# Sequencer-V10-024.net
KiCad netlist of a schematic drawn in EAGLE
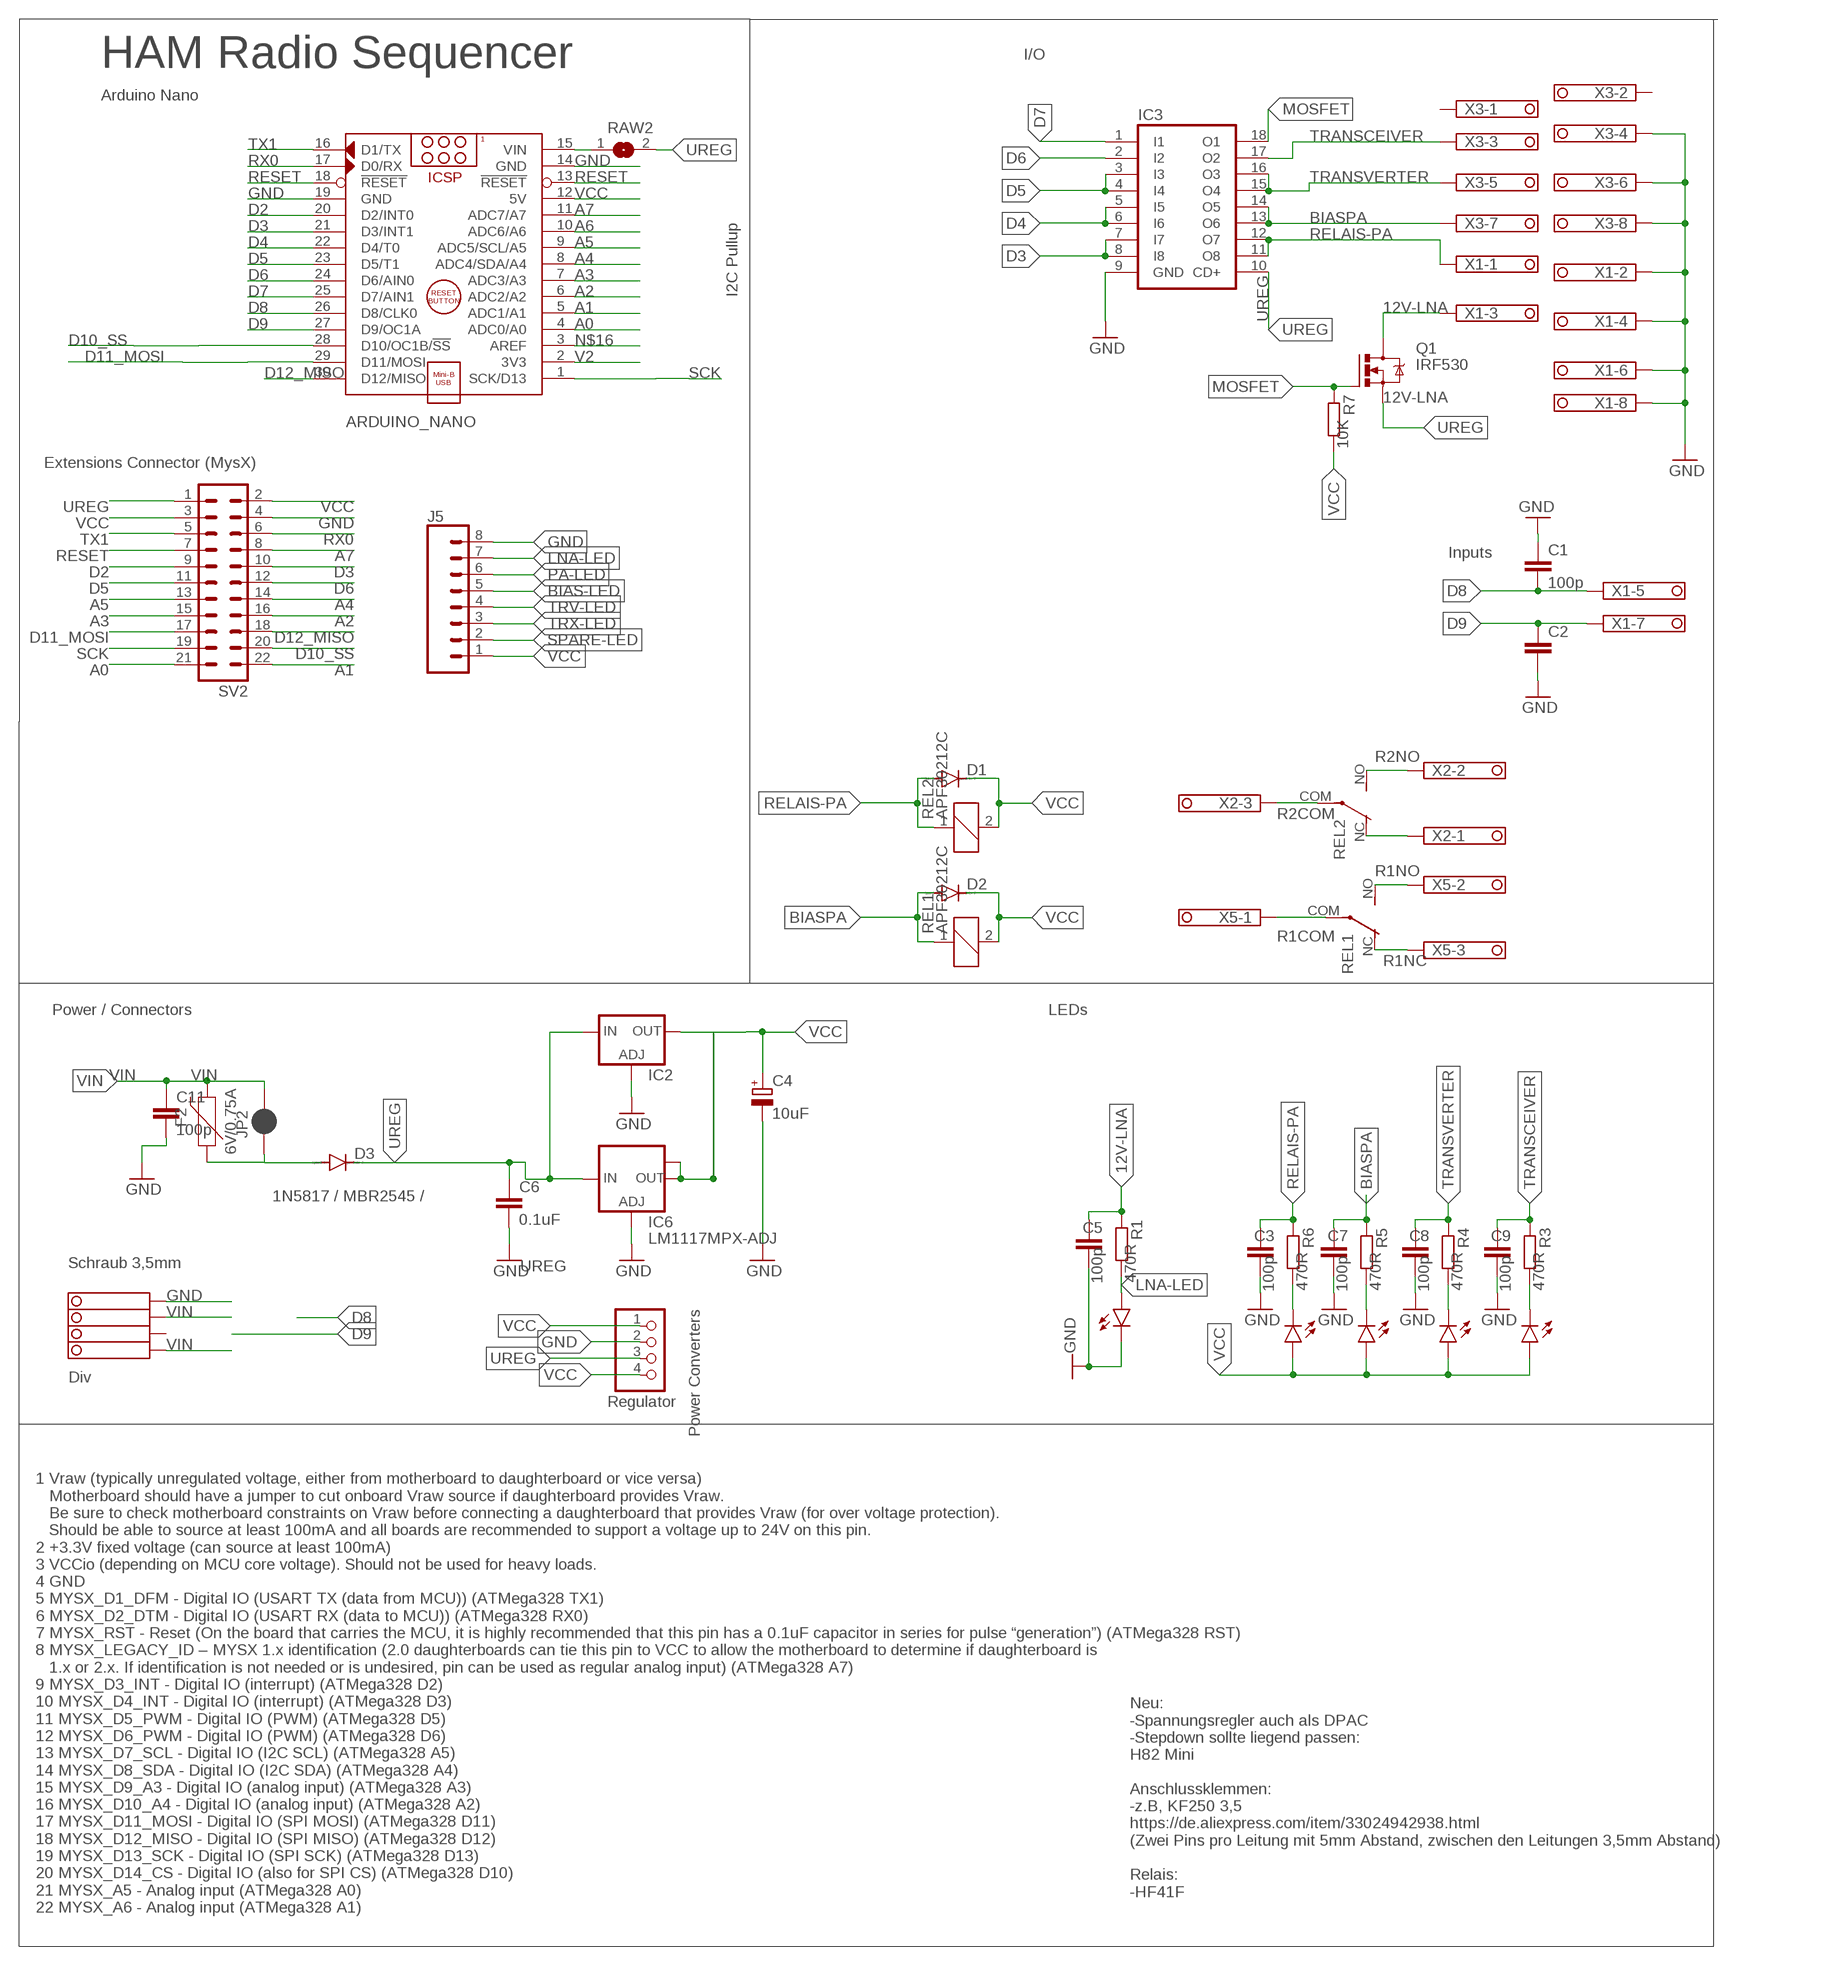
[diagram p0: schematic, sheet 1]

(export (version "E")
  (design (tool "Eeschema 10.0.6"))
  (components
    (comp (ref "ARDUINO_NANO")
      (value "ARDUINO_NANO_OHNE-BOHR")
      (footprint "eagle-import:ARDUINO_NANO")
      (libsource (lib "eagle-import") (part "ARDUINO_NANO_OHNE-BOHR"))
    )
    (comp (ref "C1")
      (value "100p")
      (footprint "eagle-import:C025-025X050")
      (libsource (lib "eagle-import") (part "C-EU025-025X050"))
    )
    (comp (ref "C2")
      (value "C-EU025-025X050")
      (footprint "eagle-import:C025-025X050")
      (libsource (lib "eagle-import") (part "C-EU025-025X050"))
    )
    (comp (ref "C3")
      (value "100p")
      (footprint "eagle-import:C025-025X050")
      (libsource (lib "eagle-import") (part "C-EU025-025X050"))
    )
    (comp (ref "C4")
      (value "10uF")
      (footprint "eagle-import:E3,5-8")
      (libsource (lib "eagle-import") (part "CPOL-EUE3.5-8"))
    )
    (comp (ref "C5")
      (value "100p")
      (footprint "eagle-import:C025-025X050")
      (libsource (lib "eagle-import") (part "C-EU025-025X050"))
    )
    (comp (ref "C6")
      (value "0.1uF")
      (footprint "eagle-import:C050-024X044")
      (libsource (lib "eagle-import") (part "C-EU050-024X044"))
    )
    (comp (ref "C7")
      (value "100p")
      (footprint "eagle-import:C025-025X050")
      (libsource (lib "eagle-import") (part "C-EU025-025X050"))
    )
    (comp (ref "C8")
      (value "100p")
      (footprint "eagle-import:C025-025X050")
      (libsource (lib "eagle-import") (part "C-EU025-025X050"))
    )
    (comp (ref "C9")
      (value "100p")
      (footprint "eagle-import:C025-025X050")
      (libsource (lib "eagle-import") (part "C-EU025-025X050"))
    )
    (comp (ref "C11")
      (value "100p")
      (footprint "eagle-import:C025-025X050")
      (libsource (lib "eagle-import") (part "C-EU025-025X050"))
    )
    (comp (ref "D1")
      (value "DIODE-D-2.5")
      (footprint "eagle-import:D-2.5")
      (libsource (lib "eagle-import") (part "DIODE-D-2.5"))
    )
    (comp (ref "D2")
      (value "DIODE-D-2.5")
      (footprint "eagle-import:D-2.5")
      (libsource (lib "eagle-import") (part "DIODE-D-2.5"))
    )
    (comp (ref "D3")
      (value "1N5817 / MBR2545 /")
      (footprint "eagle-import:D-7.5")
      (libsource (lib "eagle-import") (part "DIODE-D-7.5"))
    )
    (comp (ref "F2")
      (value "6V/0.75A")
      (footprint "eagle-import:1206")
      (libsource (lib "eagle-import") (part "PPTC_THREE-QUARTER-AMP"))
    )
    (comp (ref "IC2")
      (value "LD117ADT50TR")
      (footprint "eagle-import:DPACK")
      (libsource (lib "eagle-import") (part "LD117A?DT50TR"))
    )
    (comp (ref "IC3")
      (value "ULN2803A")
      (footprint "eagle-import:DIL18")
      (libsource (lib "eagle-import") (part "ULN2803A"))
    )
    (comp (ref "IC6")
      (value "LM1117MPX-ADJ")
      (footprint "eagle-import:SOT223")
      (libsource (lib "eagle-import") (part "LM1117MPX-ADJ"))
    )
    (comp (ref "J5")
      (value "CONN_08LOCK")
      (footprint "eagle-import:1X08_LOCK")
      (libsource (lib "eagle-import") (part "CONN_08LOCK"))
    )
    (comp (ref "JP2")
      (value "JUMPER-SMT_2_NC_PASTE_NO-SILK")
      (footprint "eagle-import:SMT-JUMPER_2_NC_PASTE_NO-SILK")
      (libsource (lib "eagle-import") (part "JUMPER-SMT_2_NC_PASTE_NO-SILK"))
    )
    (comp (ref "LED-BIAS")
      (value "LED3MM")
      (footprint "eagle-import:LED3MM")
      (libsource (lib "eagle-import") (part "LED3MM"))
    )
    (comp (ref "LED-LNA")
      (value "LED3MM")
      (footprint "eagle-import:LED3MM")
      (libsource (lib "eagle-import") (part "LED3MM"))
    )
    (comp (ref "LED-PA")
      (value "LED3MM")
      (footprint "eagle-import:LED3MM")
      (libsource (lib "eagle-import") (part "LED3MM"))
    )
    (comp (ref "LED-TRV")
      (value "LED3MM")
      (footprint "eagle-import:LED3MM")
      (libsource (lib "eagle-import") (part "LED3MM"))
    )
    (comp (ref "LED-TRX")
      (value "LED3MM")
      (footprint "eagle-import:LED3MM")
      (libsource (lib "eagle-import") (part "LED3MM"))
    )
    (comp (ref "Q1")
      (value "IRF530")
      (footprint "eagle-import:TO220BV")
      (libsource (lib "eagle-import") (part "IRF530"))
    )
    (comp (ref "R1")
      (value "470R")
      (footprint "eagle-import:0207_7")
      (libsource (lib "eagle-import") (part "R-EU_0207/7"))
    )
    (comp (ref "R3")
      (value "470R")
      (footprint "eagle-import:0207_7")
      (libsource (lib "eagle-import") (part "R-EU_0207/7"))
    )
    (comp (ref "R4")
      (value "470R")
      (footprint "eagle-import:0207_7")
      (libsource (lib "eagle-import") (part "R-EU_0207/7"))
    )
    (comp (ref "R5")
      (value "470R")
      (footprint "eagle-import:0207_7")
      (libsource (lib "eagle-import") (part "R-EU_0207/7"))
    )
    (comp (ref "R6")
      (value "470R")
      (footprint "eagle-import:0207_7")
      (libsource (lib "eagle-import") (part "R-EU_0207/7"))
    )
    (comp (ref "R7")
      (value "10K")
      (footprint "eagle-import:0207_7")
      (libsource (lib "eagle-import") (part "R-EU_0207/7"))
    )
    (comp (ref "RAW2")
      (value "SJ")
      (footprint "eagle-import:SJ")
      (libsource (lib "eagle-import") (part "SJ"))
    )
    (comp (ref "REL1")
      (value "APF30212C")
      (footprint "eagle-import:APF30212C")
      (libsource (lib "eagle-import") (part "APF30212C"))
    )
    (comp (ref "REL2")
      (value "APF30212C")
      (footprint "eagle-import:APF30212C")
      (libsource (lib "eagle-import") (part "APF30212C"))
    )
    (comp (ref "STEPDWN")
      (value "PINHD-1X04_2.54-S")
      (footprint "eagle-import:1X04-S")
      (libsource (lib "eagle-import") (part "PINHD-1X04_2.54-S"))
    )
    (comp (ref "SV2")
      (value "MA11-2")
      (footprint "eagle-import:MA11-2")
      (libsource (lib "eagle-import") (part "MA11-2"))
    )
    (comp (ref "X1")
      (value "MARTIN8X2-1751303")
      (footprint "eagle-import:1751303")
      (libsource (lib "eagle-import") (part "MARTIN8X2-1751303"))
    )
    (comp (ref "X2")
      (value "MARTIN3X2-1751303175L303-3")
      (footprint "eagle-import:1751303-3")
      (libsource (lib "eagle-import") (part "MARTIN3X2-1751303175L303-3"))
    )
    (comp (ref "X3")
      (value "MARTIN8X2-1751303")
      (footprint "eagle-import:1751303")
      (libsource (lib "eagle-import") (part "MARTIN8X2-1751303"))
    )
    (comp (ref "X4")
      (value "1751264")
      (footprint "eagle-import:1751264")
      (libsource (lib "eagle-import") (part "1751264"))
    )
    (comp (ref "X5")
      (value "MARTIN3X2-1751303175L303-3")
      (footprint "eagle-import:1751303-3")
      (libsource (lib "eagle-import") (part "MARTIN3X2-1751303175L303-3"))
    )
  )
  (nets
    (net (code "1") (name "/A0") (class "Default")
      (node (ref "ARDUINO_NANO") (pin "4") (pinfunction "ADC0/A0_4") (pintype "bidirectional"))
      (node (ref "SV2") (pin "21") (pinfunction "21_21") (pintype "passive"))
    )
    (net (code "2") (name "/A1") (class "Default")
      (node (ref "ARDUINO_NANO") (pin "5") (pinfunction "ADC1/A1_5") (pintype "bidirectional"))
      (node (ref "SV2") (pin "22") (pinfunction "22_22") (pintype "passive"))
    )
    (net (code "3") (name "/A2") (class "Default")
      (node (ref "ARDUINO_NANO") (pin "6") (pinfunction "ADC2/A2_6") (pintype "bidirectional"))
      (node (ref "SV2") (pin "16") (pinfunction "16_16") (pintype "passive"))
    )
    (net (code "4") (name "/A3") (class "Default")
      (node (ref "ARDUINO_NANO") (pin "7") (pinfunction "ADC3/A3_7") (pintype "bidirectional"))
      (node (ref "SV2") (pin "15") (pinfunction "15_15") (pintype "passive"))
    )
    (net (code "5") (name "/A4") (class "Default")
      (node (ref "ARDUINO_NANO") (pin "8") (pinfunction "ADC4/SDA/A4_8") (pintype "bidirectional"))
      (node (ref "SV2") (pin "14") (pinfunction "14_14") (pintype "passive"))
    )
    (net (code "6") (name "/A5") (class "Default")
      (node (ref "ARDUINO_NANO") (pin "9") (pinfunction "ADC5/SCL/A5_9") (pintype "bidirectional"))
      (node (ref "SV2") (pin "13") (pinfunction "13_13") (pintype "passive"))
    )
    (net (code "7") (name "/A6") (class "Default")
      (node (ref "ARDUINO_NANO") (pin "10") (pinfunction "ADC6/A6_10") (pintype "bidirectional"))
    )
    (net (code "8") (name "/A7") (class "Default")
      (node (ref "ARDUINO_NANO") (pin "11") (pinfunction "ADC7/A7_11") (pintype "bidirectional"))
      (node (ref "SV2") (pin "8") (pinfunction "8_8") (pintype "passive"))
    )
    (net (code "9") (name "/D2") (class "Default")
      (node (ref "ARDUINO_NANO") (pin "20") (pinfunction "D2/INT0_20") (pintype "bidirectional"))
      (node (ref "SV2") (pin "9") (pinfunction "9_9") (pintype "passive"))
    )
    (net (code "10") (name "/D10_SS") (class "Default")
      (node (ref "ARDUINO_NANO") (pin "28") (pinfunction "D10/OC1B/~{SS}_28") (pintype "bidirectional"))
      (node (ref "SV2") (pin "20") (pinfunction "20_20") (pintype "passive"))
    )
    (net (code "11") (name "/D11_MOSI") (class "Default")
      (node (ref "ARDUINO_NANO") (pin "29") (pinfunction "D11/MOSI_29") (pintype "bidirectional"))
      (node (ref "SV2") (pin "17") (pinfunction "17_17") (pintype "passive"))
    )
    (net (code "12") (name "/D12_MISO") (class "Default")
      (node (ref "ARDUINO_NANO") (pin "30") (pinfunction "D12/MISO_30") (pintype "bidirectional"))
      (node (ref "SV2") (pin "18") (pinfunction "18_18") (pintype "passive"))
    )
    (net (code "13") (name "/N$16") (class "Default")
      (node (ref "ARDUINO_NANO") (pin "3") (pinfunction "AREF_3") (pintype "input"))
    )
    (net (code "14") (name "/R1COM") (class "Default")
      (node (ref "REL1") (pin "COM") (pinfunction "P_COM") (pintype "passive"))
      (node (ref "X5") (pin "1") (pinfunction "K_1") (pintype "passive"))
    )
    (net (code "15") (name "/R1NC") (class "Default")
      (node (ref "REL1") (pin "NC") (pinfunction "O_NC") (pintype "passive"))
      (node (ref "X5") (pin "3") (pinfunction "K_3") (pintype "passive"))
    )
    (net (code "16") (name "/R1NO") (class "Default")
      (node (ref "REL1") (pin "NO") (pinfunction "S_NO") (pintype "passive"))
      (node (ref "X5") (pin "2") (pinfunction "K_2") (pintype "passive"))
    )
    (net (code "17") (name "/R2COM") (class "Default")
      (node (ref "REL2") (pin "COM") (pinfunction "P_COM") (pintype "passive"))
      (node (ref "X2") (pin "3") (pinfunction "K_3") (pintype "passive"))
    )
    (net (code "18") (name "/R2NO") (class "Default")
      (node (ref "REL2") (pin "NO") (pinfunction "S_NO") (pintype "passive"))
      (node (ref "X2") (pin "2") (pinfunction "K_2") (pintype "passive"))
    )
    (net (code "19") (name "/RESET") (class "Default")
      (node (ref "ARDUINO_NANO") (pin "13") (pinfunction "~{RESET}_13") (pintype "input"))
      (node (ref "ARDUINO_NANO") (pin "18") (pinfunction "~{RESET}_18") (pintype "input"))
      (node (ref "SV2") (pin "7") (pinfunction "7_7") (pintype "passive"))
    )
    (net (code "20") (name "/RX0") (class "Default")
      (node (ref "ARDUINO_NANO") (pin "17") (pinfunction "D0/RX_17") (pintype "bidirectional"))
      (node (ref "SV2") (pin "6") (pinfunction "6_6") (pintype "passive"))
    )
    (net (code "21") (name "/SCK") (class "Default")
      (node (ref "ARDUINO_NANO") (pin "1") (pinfunction "SCK/D13_1") (pintype "bidirectional"))
      (node (ref "SV2") (pin "19") (pinfunction "19_19") (pintype "passive"))
    )
    (net (code "22") (name "/TX1") (class "Default")
      (node (ref "ARDUINO_NANO") (pin "16") (pinfunction "D1/TX_16") (pintype "bidirectional"))
      (node (ref "SV2") (pin "5") (pinfunction "5_5") (pintype "passive"))
    )
    (net (code "23") (name "/V2") (class "Default")
      (node (ref "ARDUINO_NANO") (pin "2") (pinfunction "3V3_2") (pintype "output"))
    )
    (net (code "24") (name "12V-LNA") (class "Default")
      (node (ref "C5") (pin "1") (pinfunction "1_1") (pintype "passive"))
      (node (ref "Q1") (pin "D") (pinfunction "D_D") (pintype "passive"))
      (node (ref "R1") (pin "1") (pinfunction "1_1") (pintype "passive"))
      (node (ref "X1") (pin "11") (pinfunction "K_11") (pintype "passive"))
    )
    (net (code "25") (name "BIAS-LED") (class "Default")
      (node (ref "J5") (pin "5") (pinfunction "5_5") (pintype "passive"))
      (node (ref "LED-BIAS") (pin "K") (pinfunction "C_K") (pintype "passive"))
      (node (ref "R5") (pin "2") (pinfunction "2_2") (pintype "passive"))
    )
    (net (code "26") (name "BIASPA") (class "Default")
      (node (ref "C7") (pin "1") (pinfunction "1_1") (pintype "passive"))
      (node (ref "D2") (pin "A") (pinfunction "A_A") (pintype "passive"))
      (node (ref "IC3") (pin "13") (pinfunction "O6_13") (pintype "open_collector"))
      (node (ref "IC3") (pin "14") (pinfunction "O5_14") (pintype "open_collector"))
      (node (ref "R5") (pin "1") (pinfunction "1_1") (pintype "passive"))
      (node (ref "REL1") (pin "1") (pinfunction "1_1") (pintype "passive"))
      (node (ref "X3") (pin "15") (pinfunction "K_15") (pintype "passive"))
    )
    (net (code "27") (name "D3") (class "Default")
      (node (ref "ARDUINO_NANO") (pin "21") (pinfunction "D3/INT1_21") (pintype "bidirectional"))
      (node (ref "IC3") (pin "7") (pinfunction "I7_7") (pintype "input"))
      (node (ref "IC3") (pin "8") (pinfunction "I8_8") (pintype "input"))
      (node (ref "SV2") (pin "10") (pinfunction "10_10") (pintype "passive"))
    )
    (net (code "28") (name "D4") (class "Default")
      (node (ref "ARDUINO_NANO") (pin "22") (pinfunction "D4/T0_22") (pintype "bidirectional"))
      (node (ref "IC3") (pin "5") (pinfunction "I5_5") (pintype "input"))
      (node (ref "IC3") (pin "6") (pinfunction "I6_6") (pintype "input"))
    )
    (net (code "29") (name "D5") (class "Default")
      (node (ref "ARDUINO_NANO") (pin "23") (pinfunction "D5/T1_23") (pintype "bidirectional"))
      (node (ref "IC3") (pin "3") (pinfunction "I3_3") (pintype "input"))
      (node (ref "IC3") (pin "4") (pinfunction "I4_4") (pintype "input"))
      (node (ref "SV2") (pin "11") (pinfunction "11_11") (pintype "passive"))
    )
    (net (code "30") (name "D6") (class "Default")
      (node (ref "ARDUINO_NANO") (pin "24") (pinfunction "D6/AIN0_24") (pintype "bidirectional"))
      (node (ref "IC3") (pin "2") (pinfunction "I2_2") (pintype "input"))
      (node (ref "SV2") (pin "12") (pinfunction "12_12") (pintype "passive"))
    )
    (net (code "31") (name "D7") (class "Default")
      (node (ref "ARDUINO_NANO") (pin "25") (pinfunction "D7/AIN1_25") (pintype "bidirectional"))
      (node (ref "IC3") (pin "1") (pinfunction "I1_1") (pintype "input"))
    )
    (net (code "32") (name "D8") (class "Default")
      (node (ref "ARDUINO_NANO") (pin "26") (pinfunction "D8/CLK0_26") (pintype "bidirectional"))
      (node (ref "C1") (pin "2") (pinfunction "2_2") (pintype "passive"))
      (node (ref "X1") (pin "13") (pinfunction "K_13") (pintype "passive"))
    )
    (net (code "33") (name "D9") (class "Default")
      (node (ref "ARDUINO_NANO") (pin "27") (pinfunction "D9/OC1A_27") (pintype "bidirectional"))
      (node (ref "C2") (pin "1") (pinfunction "1_1") (pintype "passive"))
      (node (ref "X1") (pin "15") (pinfunction "K_15") (pintype "passive"))
    )
    (net (code "34") (name "GND") (class "Default")
      (node (ref "ARDUINO_NANO") (pin "14") (pinfunction "GND_14") (pintype "power_in"))
      (node (ref "ARDUINO_NANO") (pin "19") (pinfunction "GND_19") (pintype "power_in"))
      (node (ref "C1") (pin "1") (pinfunction "1_1") (pintype "passive"))
      (node (ref "C11") (pin "2") (pinfunction "2_2") (pintype "passive"))
      (node (ref "C2") (pin "2") (pinfunction "2_2") (pintype "passive"))
      (node (ref "C3") (pin "2") (pinfunction "2_2") (pintype "passive"))
      (node (ref "C4") (pin "-") (pinfunction "-_-") (pintype "passive"))
      (node (ref "C5") (pin "2") (pinfunction "2_2") (pintype "passive"))
      (node (ref "C6") (pin "2") (pinfunction "2_2") (pintype "passive"))
      (node (ref "C7") (pin "2") (pinfunction "2_2") (pintype "passive"))
      (node (ref "C8") (pin "2") (pinfunction "2_2") (pintype "passive"))
      (node (ref "C9") (pin "2") (pinfunction "2_2") (pintype "passive"))
      (node (ref "IC2") (pin "1") (pinfunction "ADJ_1") (pintype "input"))
      (node (ref "IC3") (pin "9") (pinfunction "GND_9") (pintype "power_in"))
      (node (ref "IC6") (pin "1") (pinfunction "ADJ_1") (pintype "input"))
      (node (ref "J5") (pin "8") (pinfunction "8_8") (pintype "passive"))
      (node (ref "LED-LNA") (pin "K") (pinfunction "C_K") (pintype "passive"))
      (node (ref "STEPDWN") (pin "2") (pinfunction "2_2") (pintype "passive"))
      (node (ref "SV2") (pin "4") (pinfunction "4_4") (pintype "passive"))
      (node (ref "X1") (pin "10") (pinfunction "K_10") (pintype "passive"))
      (node (ref "X1") (pin "12") (pinfunction "K_12") (pintype "passive"))
      (node (ref "X1") (pin "14") (pinfunction "K_14") (pintype "passive"))
      (node (ref "X1") (pin "16") (pinfunction "K_16") (pintype "passive"))
      (node (ref "X3") (pin "12") (pinfunction "K_12") (pintype "passive"))
      (node (ref "X3") (pin "14") (pinfunction "K_14") (pintype "passive"))
      (node (ref "X3") (pin "16") (pinfunction "K_16") (pintype "passive"))
      (node (ref "X4") (pin "4") (pinfunction "K_4") (pintype "passive"))
    )
    (net (code "35") (name "LNA-LED") (class "Default")
      (node (ref "J5") (pin "7") (pinfunction "7_7") (pintype "passive"))
      (node (ref "LED-LNA") (pin "A") (pinfunction "A_A") (pintype "passive"))
      (node (ref "R1") (pin "2") (pinfunction "2_2") (pintype "passive"))
    )
    (net (code "36") (name "MOSFET") (class "Default")
      (node (ref "IC3") (pin "18") (pinfunction "O1_18") (pintype "open_collector"))
      (node (ref "Q1") (pin "G") (pinfunction "G_G") (pintype "passive"))
      (node (ref "R7") (pin "1") (pinfunction "1_1") (pintype "passive"))
    )
    (net (code "37") (name "Net-(ARDUINO_NANO-VIN)") (class "Default")
      (node (ref "ARDUINO_NANO") (pin "15") (pinfunction "VIN_15") (pintype "power_in"))
      (node (ref "RAW2") (pin "1") (pinfunction "1_1") (pintype "passive"))
    )
    (net (code "38") (name "Net-(D3-PadA)") (class "Default")
      (node (ref "D3") (pin "A") (pinfunction "A_A") (pintype "passive"))
      (node (ref "F2") (pin "1") (pinfunction "1_1") (pintype "bidirectional"))
      (node (ref "JP2") (pin "1") (pinfunction "1_1") (pintype "passive"))
    )
    (net (code "39") (name "Net-(REL2B-O)") (class "Default")
      (node (ref "REL2") (pin "NC") (pinfunction "O_NC") (pintype "passive"))
      (node (ref "X2") (pin "1") (pinfunction "K_1") (pintype "passive"))
    )
    (net (code "40") (name "PA-LED") (class "Default")
      (node (ref "J5") (pin "6") (pinfunction "6_6") (pintype "passive"))
      (node (ref "LED-PA") (pin "K") (pinfunction "C_K") (pintype "passive"))
      (node (ref "R6") (pin "2") (pinfunction "2_2") (pintype "passive"))
    )
    (net (code "41") (name "RELAIS-PA") (class "Default")
      (node (ref "C3") (pin "1") (pinfunction "1_1") (pintype "passive"))
      (node (ref "D1") (pin "A") (pinfunction "A_A") (pintype "passive"))
      (node (ref "IC3") (pin "11") (pinfunction "O8_11") (pintype "open_collector"))
      (node (ref "IC3") (pin "12") (pinfunction "O7_12") (pintype "open_collector"))
      (node (ref "R6") (pin "1") (pinfunction "1_1") (pintype "passive"))
      (node (ref "REL2") (pin "1") (pinfunction "1_1") (pintype "passive"))
      (node (ref "X1") (pin "9") (pinfunction "K_9") (pintype "passive"))
    )
    (net (code "42") (name "SPARE-LED") (class "Default")
      (node (ref "J5") (pin "2") (pinfunction "2_2") (pintype "passive"))
    )
    (net (code "43") (name "TRANSCEIVER") (class "Default")
      (node (ref "C9") (pin "1") (pinfunction "1_1") (pintype "passive"))
      (node (ref "IC3") (pin "17") (pinfunction "O2_17") (pintype "open_collector"))
      (node (ref "R3") (pin "1") (pinfunction "1_1") (pintype "passive"))
      (node (ref "X3") (pin "11") (pinfunction "K_11") (pintype "passive"))
    )
    (net (code "44") (name "TRANSVERTER") (class "Default")
      (node (ref "C8") (pin "1") (pinfunction "1_1") (pintype "passive"))
      (node (ref "IC3") (pin "15") (pinfunction "O4_15") (pintype "open_collector"))
      (node (ref "IC3") (pin "16") (pinfunction "O3_16") (pintype "open_collector"))
      (node (ref "R4") (pin "1") (pinfunction "1_1") (pintype "passive"))
      (node (ref "X3") (pin "13") (pinfunction "K_13") (pintype "passive"))
    )
    (net (code "45") (name "TRV-LED") (class "Default")
      (node (ref "J5") (pin "4") (pinfunction "4_4") (pintype "passive"))
      (node (ref "LED-TRV") (pin "K") (pinfunction "C_K") (pintype "passive"))
      (node (ref "R4") (pin "2") (pinfunction "2_2") (pintype "passive"))
    )
    (net (code "46") (name "TRX-LED") (class "Default")
      (node (ref "J5") (pin "3") (pinfunction "3_3") (pintype "passive"))
      (node (ref "LED-TRX") (pin "K") (pinfunction "C_K") (pintype "passive"))
      (node (ref "R3") (pin "2") (pinfunction "2_2") (pintype "passive"))
    )
    (net (code "47") (name "UREG") (class "Default")
      (node (ref "C6") (pin "1") (pinfunction "1_1") (pintype "passive"))
      (node (ref "D3") (pin "C") (pinfunction "C_C") (pintype "passive"))
      (node (ref "IC2") (pin "3") (pinfunction "IN_3") (pintype "input"))
      (node (ref "IC3") (pin "10") (pinfunction "CD+_10") (pintype "passive"))
      (node (ref "IC6") (pin "3") (pinfunction "IN_3") (pintype "input"))
      (node (ref "Q1") (pin "S") (pinfunction "S_S") (pintype "passive"))
      (node (ref "RAW2") (pin "2") (pinfunction "2_2") (pintype "passive"))
      (node (ref "STEPDWN") (pin "3") (pinfunction "3_3") (pintype "passive"))
      (node (ref "SV2") (pin "1") (pinfunction "1_1") (pintype "passive"))
    )
    (net (code "48") (name "VCC") (class "Default")
      (node (ref "ARDUINO_NANO") (pin "12") (pinfunction "5V_12") (pintype "power_in"))
      (node (ref "C4") (pin "+") (pinfunction "+_+") (pintype "passive"))
      (node (ref "D1") (pin "C") (pinfunction "C_C") (pintype "passive"))
      (node (ref "D2") (pin "C") (pinfunction "C_C") (pintype "passive"))
      (node (ref "IC2") (pin "4") (pinfunction "OUT_4") (pintype "passive"))
      (node (ref "IC6") (pin "2") (pinfunction "OUT_2") (pintype "passive"))
      (node (ref "IC6") (pin "TAB") (pinfunction "OUT1_TAB") (pintype "passive"))
      (node (ref "J5") (pin "1") (pinfunction "1_1") (pintype "passive"))
      (node (ref "LED-BIAS") (pin "A") (pinfunction "A_A") (pintype "passive"))
      (node (ref "LED-PA") (pin "A") (pinfunction "A_A") (pintype "passive"))
      (node (ref "LED-TRV") (pin "A") (pinfunction "A_A") (pintype "passive"))
      (node (ref "LED-TRX") (pin "A") (pinfunction "A_A") (pintype "passive"))
      (node (ref "R7") (pin "2") (pinfunction "2_2") (pintype "passive"))
      (node (ref "REL1") (pin "2") (pinfunction "2_2") (pintype "passive"))
      (node (ref "REL2") (pin "2") (pinfunction "2_2") (pintype "passive"))
      (node (ref "STEPDWN") (pin "1") (pinfunction "1_1") (pintype "passive"))
      (node (ref "STEPDWN") (pin "4") (pinfunction "4_4") (pintype "passive"))
      (node (ref "SV2") (pin "2") (pinfunction "2_2") (pintype "passive"))
      (node (ref "SV2") (pin "3") (pinfunction "3_3") (pintype "passive"))
    )
    (net (code "49") (name "VIN") (class "Default")
      (node (ref "C11") (pin "1") (pinfunction "1_1") (pintype "passive"))
      (node (ref "F2") (pin "2") (pinfunction "2_2") (pintype "bidirectional"))
      (node (ref "JP2") (pin "2") (pinfunction "2_2") (pintype "passive"))
      (node (ref "X4") (pin "1") (pinfunction "K_1") (pintype "passive"))
      (node (ref "X4") (pin "3") (pinfunction "K_3") (pintype "passive"))
    )
    (net (code "50") (name "unconnected-(X3A-K-Pad9)") (class "Default")
      (node (ref "X3") (pin "9") (pinfunction "K_9") (pintype "passive"))
    )
    (net (code "51") (name "unconnected-(X3B-K-Pad10)") (class "Default")
      (node (ref "X3") (pin "10") (pinfunction "K_10") (pintype "passive"))
    )
    (net (code "52") (name "unconnected-(X4B-K-Pad2)") (class "Default")
      (node (ref "X4") (pin "2") (pinfunction "K_2") (pintype "passive"))
    )
  )
)
